# esc.net
KiCad netlist of a schematic drawn in Altium Designer
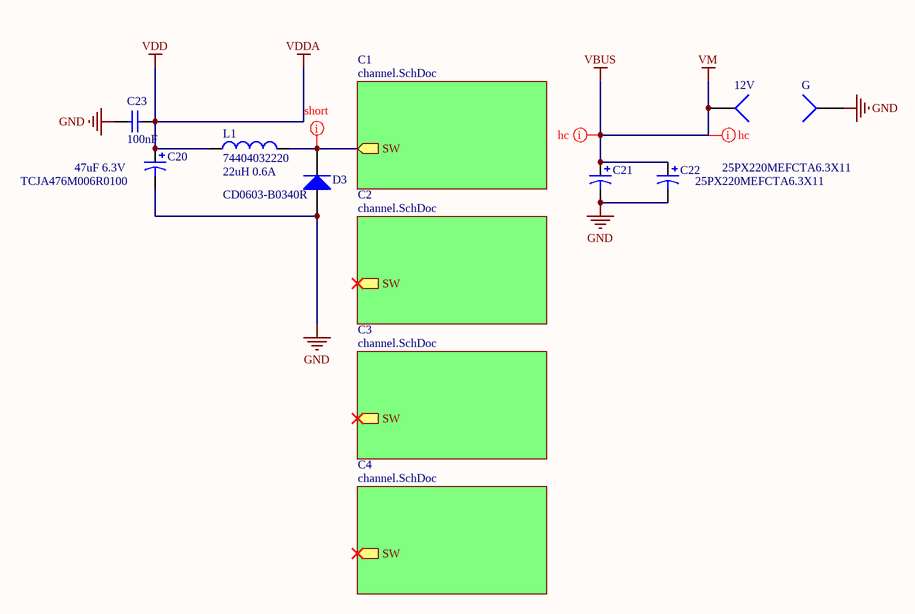
[diagram p0: esc.SchDoc]

(export (version "E")
  (design (tool "Eeschema 10.0.6"))
  (components
    (comp (ref "12V")
      (value "12V")
      (footprint "large_pin")
      (description "Socket")
      (fields (field (name "PUBLISHER") "Altium Limited"))
      (libsource (lib "Miscellaneous Connectors") (part "Socket"))
    )
    (comp (ref "C20")
      (value "TCJA476M006R0100")
      (footprint "my_1206_pol")
      (description "Polarized Capacitor (Surface Mount)")
      (fields (field (name "ALTIUM_VALUE") "47uF 6.3V") (field (name "PUBLISHER") "Altium Limited"))
      (libsource (lib "Miscellaneous Devices") (part "Cap Pol3"))
    )
    (comp (ref "C21")
      (value "25PX220MEFCTA6.3X11")
      (footprint "rad_2.5mm_0.7mm")
      (description "Polarized Capacitor (Surface Mount)")
      (fields (field (name "PUBLISHER") "Altium Limited"))
      (libsource (lib "Miscellaneous Devices") (part "Cap Pol3"))
    )
    (comp (ref "C22")
      (value "25PX220MEFCTA6.3X11")
      (footprint "rad_2.5mm_0.7mm")
      (description "Polarized Capacitor (Surface Mount)")
      (fields (field (name "PUBLISHER") "Altium Limited"))
      (libsource (lib "Miscellaneous Devices") (part "Cap Pol3"))
    )
    (comp (ref "C23")
      (value "100nF")
      (description "Capacitor")
      (fields (field (name "PUBLISHER") "Altium Limited"))
      (libsource (lib "Miscellaneous Devices") (part "Cap"))
    )
    (comp (ref "D3")
      (value "CD0603-B0340R")
      (footprint "my_0603")
      (description "Default Diode")
      (fields (field (name "PUBLISHER") "Altium Limited"))
      (libsource (lib "Miscellaneous Devices") (part "Diode"))
    )
    (comp (ref "G")
      (value "G")
      (footprint "large_pin")
      (description "Socket")
      (fields (field (name "PUBLISHER") "Altium Limited"))
      (libsource (lib "Miscellaneous Connectors") (part "Socket"))
    )
    (comp (ref "L1")
      (value "74404032220")
      (footprint "IND_3_3")
      (description "Inductor")
      (fields (field (name "ALTIUM_VALUE") "22uH 0.6A") (field (name "PUBLISHER") "Altium Limited"))
      (libsource (lib "Miscellaneous Devices") (part "Inductor"))
    )
  )
  (nets
    (net (code "1") (name "/SW") (class "Default")
      (node (ref "D3") (pin "2") (pinfunction "K_2") (pintype "passive"))
      (node (ref "L1") (pin "2") (pinfunction "2_2") (pintype "passive"))
    )
    (net (code "5") (name "GND") (class "Default")
      (node (ref "C20") (pin "2") (pinfunction "2_2") (pintype "passive"))
      (node (ref "C21") (pin "2") (pinfunction "2_2") (pintype "passive"))
      (node (ref "C22") (pin "2") (pinfunction "2_2") (pintype "passive"))
      (node (ref "C23") (pin "1") (pinfunction "1_1") (pintype "passive"))
      (node (ref "D3") (pin "1") (pinfunction "A_1") (pintype "passive"))
      (node (ref "G") (pin "1") (pinfunction "1_1") (pintype "passive"))
    )
    (net (code "6") (name "VBUS") (class "Default")
      (node (ref "12V") (pin "1") (pinfunction "1_1") (pintype "passive"))
      (node (ref "C21") (pin "1") (pinfunction "1_1") (pintype "passive"))
      (node (ref "C22") (pin "1") (pinfunction "1_1") (pintype "passive"))
    )
    (net (code "7") (name "VDD") (class "Default")
      (node (ref "C20") (pin "1") (pinfunction "1_1") (pintype "passive"))
      (node (ref "C23") (pin "2") (pinfunction "2_2") (pintype "passive"))
      (node (ref "L1") (pin "1") (pinfunction "1_1") (pintype "passive"))
    )
  )
)
